# darkgame-controller-norj45.net
KiCad netlist of a schematic drawn in EAGLE
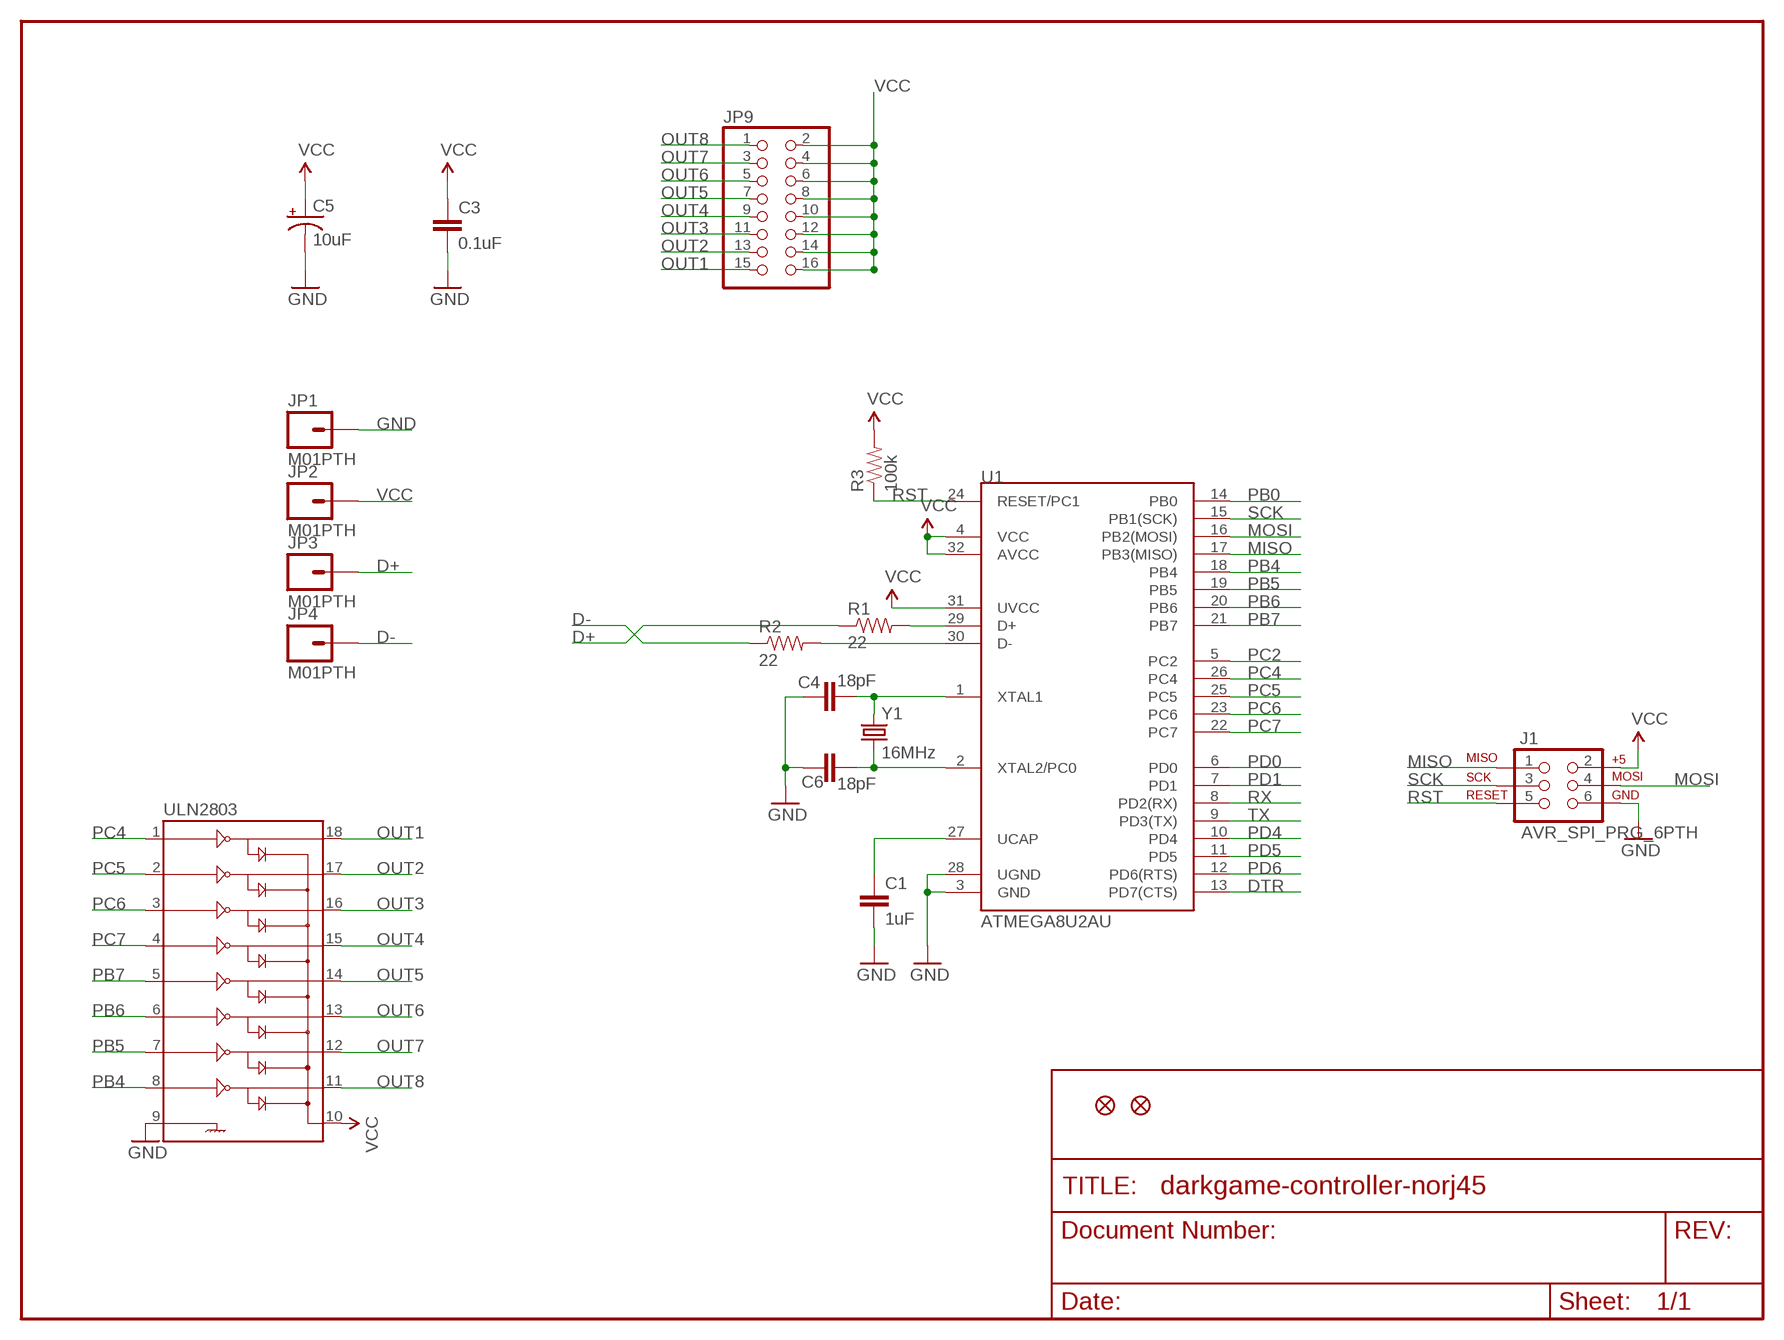
[diagram p0: schematic, sheet 1]

(export (version "E")
  (design (tool "Eeschema 10.0.6"))
  (components
    (comp (ref "C1")
      (value "1uF")
      (footprint "eagle-import:0805")
      (libsource (lib "eagle-import") (part "CAP0805"))
    )
    (comp (ref "C3")
      (value "0.1uF")
      (footprint "eagle-import:0805")
      (libsource (lib "eagle-import") (part "CAP0805"))
    )
    (comp (ref "C4")
      (value "18pF")
      (footprint "eagle-import:0805")
      (libsource (lib "eagle-import") (part "CAP0805"))
    )
    (comp (ref "C5")
      (value "10uF")
      (footprint "eagle-import:EIA3216")
      (libsource (lib "eagle-import") (part "CAP_POL1206"))
    )
    (comp (ref "C6")
      (value "18pF")
      (footprint "eagle-import:0805")
      (libsource (lib "eagle-import") (part "CAP0805"))
    )
    (comp (ref "J1")
      (value "AVR_SPI_PRG_6PTH")
      (footprint "eagle-import:2X3")
      (libsource (lib "eagle-import") (part "AVR_SPI_PRG_6PTH"))
    )
    (comp (ref "JP1")
      (value "M01PTH")
      (footprint "eagle-import:1X01")
      (libsource (lib "eagle-import") (part "M01PTH"))
    )
    (comp (ref "JP2")
      (value "M01PTH")
      (footprint "eagle-import:1X01")
      (libsource (lib "eagle-import") (part "M01PTH"))
    )
    (comp (ref "JP3")
      (value "M01PTH")
      (footprint "eagle-import:1X01")
      (libsource (lib "eagle-import") (part "M01PTH"))
    )
    (comp (ref "JP4")
      (value "M01PTH")
      (footprint "eagle-import:1X01")
      (libsource (lib "eagle-import") (part "M01PTH"))
    )
    (comp (ref "JP6")
      (value "FIDUCIAL1X2")
      (footprint "eagle-import:FIDUCIAL-1X2")
      (libsource (lib "eagle-import") (part "FIDUCIAL1X2"))
    )
    (comp (ref "JP7")
      (value "FIDUCIAL1X2")
      (footprint "eagle-import:FIDUCIAL-1X2")
      (libsource (lib "eagle-import") (part "FIDUCIAL1X2"))
    )
    (comp (ref "JP9")
      (value "PINHD-2X8")
      (footprint "eagle-import:2X08")
      (libsource (lib "eagle-import") (part "PINHD-2X8"))
    )
    (comp (ref "R1")
      (value "22")
      (footprint "eagle-import:0805")
      (libsource (lib "eagle-import") (part "RESISTOR0805-RES"))
    )
    (comp (ref "R2")
      (value "22")
      (footprint "eagle-import:0805")
      (libsource (lib "eagle-import") (part "RESISTOR0805-RES"))
    )
    (comp (ref "R3")
      (value "100k")
      (footprint "eagle-import:0805")
      (libsource (lib "eagle-import") (part "RESISTOR0805-RES"))
    )
    (comp (ref "U1")
      (value "ATMEGA8U2AU")
      (footprint "eagle-import:TQFP32-08")
      (libsource (lib "eagle-import") (part "ATMEGA8U2AU"))
    )
    (comp (ref "ULN2803")
      (value "ULN2803SOICW")
      (footprint "eagle-import:SO18L")
      (libsource (lib "eagle-import") (part "ULN2803SOICW"))
    )
    (comp (ref "Y1")
      (value "16MHz")
      (footprint "eagle-import:CRYSTAL-SMD-5X3")
      (libsource (lib "eagle-import") (part "CRYSTAL5X3"))
    )
  )
  (nets
    (net (code "1") (name "/D+") (class "Default")
      (node (ref "JP3") (pin "1") (pinfunction "1_1") (pintype "passive"))
      (node (ref "R1") (pin "1") (pinfunction "1_1") (pintype "passive"))
    )
    (net (code "2") (name "/D-") (class "Default")
      (node (ref "JP4") (pin "1") (pinfunction "1_1") (pintype "passive"))
      (node (ref "R2") (pin "1") (pinfunction "1_1") (pintype "passive"))
    )
    (net (code "3") (name "/DTR") (class "Default")
      (node (ref "U1") (pin "13") (pinfunction "PD7(CTS)_13") (pintype "bidirectional"))
    )
    (net (code "4") (name "/MISO") (class "Default")
      (node (ref "J1") (pin "1") (pinfunction "1_1") (pintype "passive"))
      (node (ref "U1") (pin "17") (pinfunction "PB3(MISO)_17") (pintype "bidirectional"))
    )
    (net (code "5") (name "/MOSI") (class "Default")
      (node (ref "J1") (pin "4") (pinfunction "4_4") (pintype "passive"))
      (node (ref "U1") (pin "16") (pinfunction "PB2(MOSI)_16") (pintype "bidirectional"))
    )
    (net (code "6") (name "/OUT1") (class "Default")
      (node (ref "JP9") (pin "15") (pinfunction "15_15") (pintype "passive"))
      (node (ref "ULN2803") (pin "18") (pinfunction "18_18") (pintype "bidirectional"))
    )
    (net (code "7") (name "/OUT2") (class "Default")
      (node (ref "JP9") (pin "13") (pinfunction "13_13") (pintype "passive"))
      (node (ref "ULN2803") (pin "17") (pinfunction "17_17") (pintype "bidirectional"))
    )
    (net (code "8") (name "/OUT3") (class "Default")
      (node (ref "JP9") (pin "11") (pinfunction "11_11") (pintype "passive"))
      (node (ref "ULN2803") (pin "16") (pinfunction "16_16") (pintype "bidirectional"))
    )
    (net (code "9") (name "/OUT4") (class "Default")
      (node (ref "JP9") (pin "9") (pinfunction "9_9") (pintype "passive"))
      (node (ref "ULN2803") (pin "15") (pinfunction "15_15") (pintype "bidirectional"))
    )
    (net (code "10") (name "/OUT5") (class "Default")
      (node (ref "JP9") (pin "7") (pinfunction "7_7") (pintype "passive"))
      (node (ref "ULN2803") (pin "14") (pinfunction "14_14") (pintype "bidirectional"))
    )
    (net (code "11") (name "/OUT6") (class "Default")
      (node (ref "JP9") (pin "5") (pinfunction "5_5") (pintype "passive"))
      (node (ref "ULN2803") (pin "13") (pinfunction "13_13") (pintype "bidirectional"))
    )
    (net (code "12") (name "/OUT7") (class "Default")
      (node (ref "JP9") (pin "3") (pinfunction "3_3") (pintype "passive"))
      (node (ref "ULN2803") (pin "12") (pinfunction "12_12") (pintype "bidirectional"))
    )
    (net (code "13") (name "/OUT8") (class "Default")
      (node (ref "JP9") (pin "1") (pinfunction "1_1") (pintype "passive"))
      (node (ref "ULN2803") (pin "11") (pinfunction "11_11") (pintype "bidirectional"))
    )
    (net (code "14") (name "/PB0") (class "Default")
      (node (ref "U1") (pin "14") (pinfunction "PB0_14") (pintype "bidirectional"))
    )
    (net (code "15") (name "/PB4") (class "Default")
      (node (ref "U1") (pin "18") (pinfunction "PB4_18") (pintype "bidirectional"))
      (node (ref "ULN2803") (pin "8") (pinfunction "8_8") (pintype "bidirectional"))
    )
    (net (code "16") (name "/PB5") (class "Default")
      (node (ref "U1") (pin "19") (pinfunction "PB5_19") (pintype "bidirectional"))
      (node (ref "ULN2803") (pin "7") (pinfunction "7_7") (pintype "bidirectional"))
    )
    (net (code "17") (name "/PB6") (class "Default")
      (node (ref "U1") (pin "20") (pinfunction "PB6_20") (pintype "bidirectional"))
      (node (ref "ULN2803") (pin "6") (pinfunction "6_6") (pintype "bidirectional"))
    )
    (net (code "18") (name "/PB7") (class "Default")
      (node (ref "U1") (pin "21") (pinfunction "PB7_21") (pintype "bidirectional"))
      (node (ref "ULN2803") (pin "5") (pinfunction "5_5") (pintype "bidirectional"))
    )
    (net (code "19") (name "/PC2") (class "Default")
      (node (ref "U1") (pin "5") (pinfunction "PC2_5") (pintype "bidirectional"))
    )
    (net (code "20") (name "/PC4") (class "Default")
      (node (ref "U1") (pin "26") (pinfunction "PC4_26") (pintype "bidirectional"))
      (node (ref "ULN2803") (pin "1") (pinfunction "1_1") (pintype "bidirectional"))
    )
    (net (code "21") (name "/PC5") (class "Default")
      (node (ref "U1") (pin "25") (pinfunction "PC5_25") (pintype "bidirectional"))
      (node (ref "ULN2803") (pin "2") (pinfunction "2_2") (pintype "bidirectional"))
    )
    (net (code "22") (name "/PC6") (class "Default")
      (node (ref "U1") (pin "23") (pinfunction "PC6_23") (pintype "bidirectional"))
      (node (ref "ULN2803") (pin "3") (pinfunction "3_3") (pintype "bidirectional"))
    )
    (net (code "23") (name "/PC7") (class "Default")
      (node (ref "U1") (pin "22") (pinfunction "PC7_22") (pintype "bidirectional"))
      (node (ref "ULN2803") (pin "4") (pinfunction "4_4") (pintype "bidirectional"))
    )
    (net (code "24") (name "/PD0") (class "Default")
      (node (ref "U1") (pin "6") (pinfunction "PD0_6") (pintype "bidirectional"))
    )
    (net (code "25") (name "/PD1") (class "Default")
      (node (ref "U1") (pin "7") (pinfunction "PD1_7") (pintype "bidirectional"))
    )
    (net (code "26") (name "/PD4") (class "Default")
      (node (ref "U1") (pin "10") (pinfunction "PD4_10") (pintype "bidirectional"))
    )
    (net (code "27") (name "/PD5") (class "Default")
      (node (ref "U1") (pin "11") (pinfunction "PD5_11") (pintype "bidirectional"))
    )
    (net (code "28") (name "/PD6") (class "Default")
      (node (ref "U1") (pin "12") (pinfunction "PD6(RTS)_12") (pintype "bidirectional"))
    )
    (net (code "29") (name "/RST") (class "Default")
      (node (ref "J1") (pin "5") (pinfunction "5_5") (pintype "passive"))
      (node (ref "R3") (pin "1") (pinfunction "1_1") (pintype "passive"))
      (node (ref "U1") (pin "24") (pinfunction "RESET/PC1_24") (pintype "bidirectional"))
    )
    (net (code "30") (name "/RX") (class "Default")
      (node (ref "U1") (pin "8") (pinfunction "PD2(RX)_8") (pintype "bidirectional"))
    )
    (net (code "31") (name "/SCK") (class "Default")
      (node (ref "J1") (pin "3") (pinfunction "3_3") (pintype "passive"))
      (node (ref "U1") (pin "15") (pinfunction "PB1(SCK)_15") (pintype "bidirectional"))
    )
    (net (code "32") (name "/TX") (class "Default")
      (node (ref "U1") (pin "9") (pinfunction "PD3(TX)_9") (pintype "bidirectional"))
    )
    (net (code "33") (name "GND") (class "Default")
      (node (ref "C1") (pin "2") (pinfunction "2_2") (pintype "passive"))
      (node (ref "C3") (pin "2") (pinfunction "2_2") (pintype "passive"))
      (node (ref "C4") (pin "2") (pinfunction "2_2") (pintype "passive"))
      (node (ref "C5") (pin "C") (pinfunction "-_C") (pintype "passive"))
      (node (ref "C6") (pin "2") (pinfunction "2_2") (pintype "passive"))
      (node (ref "J1") (pin "6") (pinfunction "6_6") (pintype "passive"))
      (node (ref "JP1") (pin "1") (pinfunction "1_1") (pintype "passive"))
      (node (ref "U1") (pin "28") (pinfunction "UGND_28") (pintype "bidirectional"))
      (node (ref "U1") (pin "3") (pinfunction "GND_3") (pintype "bidirectional"))
      (node (ref "ULN2803") (pin "9") (pinfunction "9_9") (pintype "bidirectional"))
    )
    (net (code "34") (name "Net-(U1-D+)") (class "Default")
      (node (ref "R1") (pin "2") (pinfunction "2_2") (pintype "passive"))
      (node (ref "U1") (pin "29") (pinfunction "D+_29") (pintype "bidirectional"))
    )
    (net (code "35") (name "Net-(U1-D-)") (class "Default")
      (node (ref "R2") (pin "2") (pinfunction "2_2") (pintype "passive"))
      (node (ref "U1") (pin "30") (pinfunction "D-_30") (pintype "bidirectional"))
    )
    (net (code "36") (name "Net-(U1-UCAP)") (class "Default")
      (node (ref "C1") (pin "1") (pinfunction "1_1") (pintype "passive"))
      (node (ref "U1") (pin "27") (pinfunction "UCAP_27") (pintype "bidirectional"))
    )
    (net (code "37") (name "Net-(U1-XTAL1)") (class "Default")
      (node (ref "C4") (pin "1") (pinfunction "1_1") (pintype "passive"))
      (node (ref "U1") (pin "1") (pinfunction "XTAL1_1") (pintype "bidirectional"))
      (node (ref "Y1") (pin "3") (pinfunction "2_3") (pintype "passive"))
    )
    (net (code "38") (name "Net-(U1-XTAL2{slash}PC0)") (class "Default")
      (node (ref "C6") (pin "1") (pinfunction "1_1") (pintype "passive"))
      (node (ref "U1") (pin "2") (pinfunction "XTAL2/PC0_2") (pintype "bidirectional"))
      (node (ref "Y1") (pin "1") (pinfunction "1_1") (pintype "passive"))
    )
    (net (code "39") (name "VCC") (class "Default")
      (node (ref "C3") (pin "1") (pinfunction "1_1") (pintype "passive"))
      (node (ref "C5") (pin "A") (pinfunction "+_A") (pintype "passive"))
      (node (ref "J1") (pin "2") (pinfunction "2_2") (pintype "passive"))
      (node (ref "JP2") (pin "1") (pinfunction "1_1") (pintype "passive"))
      (node (ref "JP9") (pin "10") (pinfunction "10_10") (pintype "passive"))
      (node (ref "JP9") (pin "12") (pinfunction "12_12") (pintype "passive"))
      (node (ref "JP9") (pin "14") (pinfunction "14_14") (pintype "passive"))
      (node (ref "JP9") (pin "16") (pinfunction "16_16") (pintype "passive"))
      (node (ref "JP9") (pin "2") (pinfunction "2_2") (pintype "passive"))
      (node (ref "JP9") (pin "4") (pinfunction "4_4") (pintype "passive"))
      (node (ref "JP9") (pin "6") (pinfunction "6_6") (pintype "passive"))
      (node (ref "JP9") (pin "8") (pinfunction "8_8") (pintype "passive"))
      (node (ref "R3") (pin "2") (pinfunction "2_2") (pintype "passive"))
      (node (ref "U1") (pin "31") (pinfunction "UVCC_31") (pintype "bidirectional"))
      (node (ref "U1") (pin "32") (pinfunction "AVCC_32") (pintype "bidirectional"))
      (node (ref "U1") (pin "4") (pinfunction "VCC_4") (pintype "bidirectional"))
      (node (ref "ULN2803") (pin "10") (pinfunction "10_10") (pintype "bidirectional"))
    )
  )
)
